# lickometer_1_0.net
KiCad netlist of a schematic drawn in EAGLE
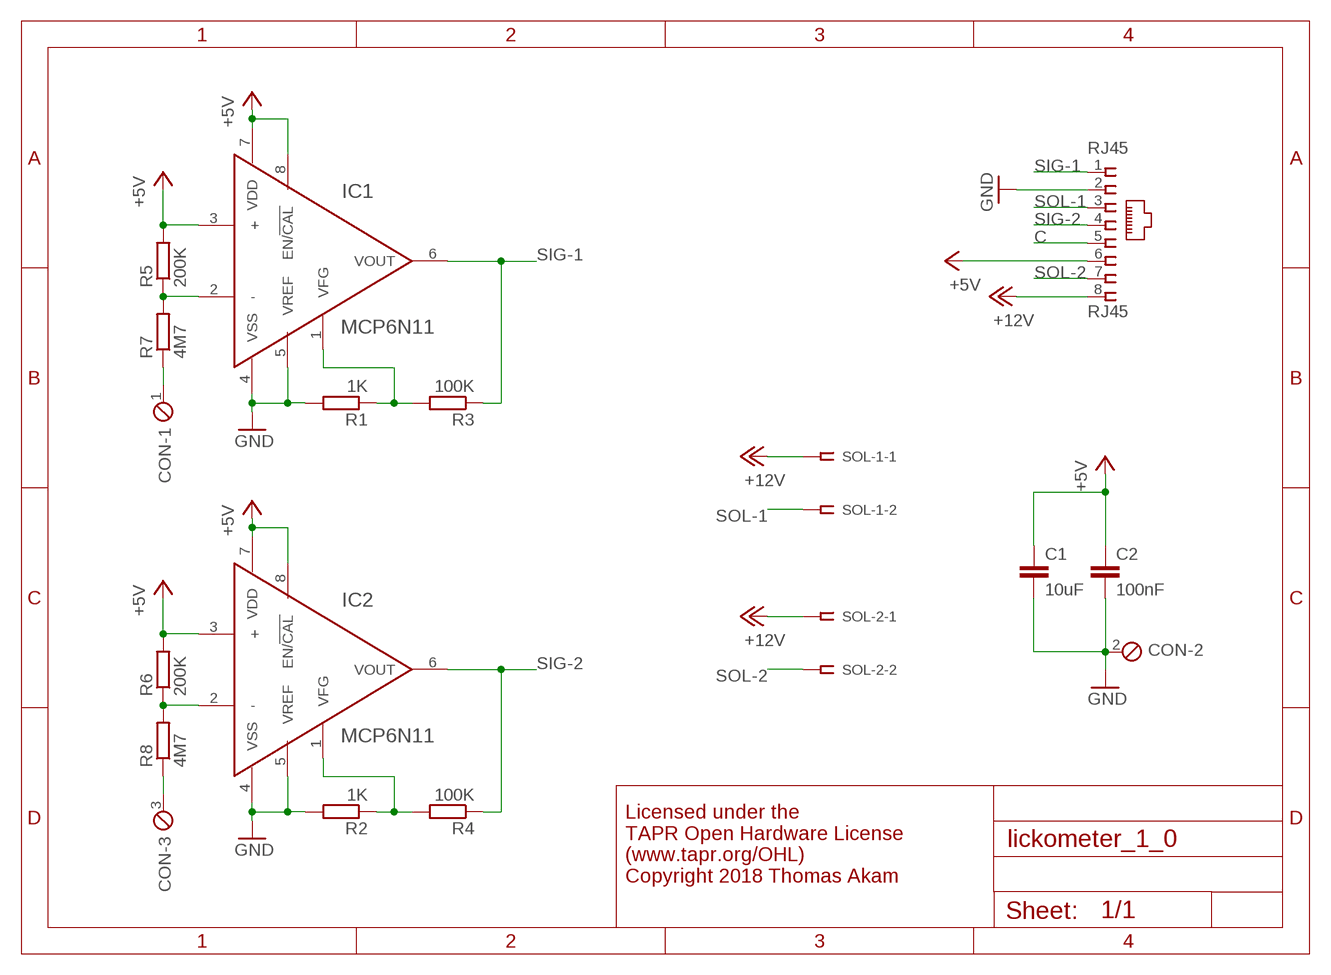
[diagram p0: schematic, sheet 1]

(export (version "E")
  (design (tool "Eeschema 10.0.6"))
  (components
    (comp (ref "C1")
      (value "10uF")
      (footprint "eagle-import:C1206")
      (libsource (lib "eagle-import") (part "C-EUC1206"))
    )
    (comp (ref "C2")
      (value "100nF")
      (footprint "eagle-import:C0805")
      (libsource (lib "eagle-import") (part "C-EUC0805"))
    )
    (comp (ref "CON")
      (value "MPT3")
      (footprint "eagle-import:3POL254")
      (libsource (lib "eagle-import") (part "MPT3"))
    )
    (comp (ref "IC1")
      (value "MCP6N11")
      (footprint "eagle-import:SOIC127P600X175-8N")
      (libsource (lib "eagle-import") (part "MCP6N11"))
    )
    (comp (ref "IC2")
      (value "MCP6N11")
      (footprint "eagle-import:SOIC127P600X175-8N")
      (libsource (lib "eagle-import") (part "MCP6N11"))
    )
    (comp (ref "R1")
      (value "1K")
      (footprint "eagle-import:R0805")
      (libsource (lib "eagle-import") (part "R-EU_R0805"))
    )
    (comp (ref "R2")
      (value "1K")
      (footprint "eagle-import:R0805")
      (libsource (lib "eagle-import") (part "R-EU_R0805"))
    )
    (comp (ref "R3")
      (value "100K")
      (footprint "eagle-import:R0805")
      (libsource (lib "eagle-import") (part "R-EU_R0805"))
    )
    (comp (ref "R4")
      (value "100K")
      (footprint "eagle-import:R0805")
      (libsource (lib "eagle-import") (part "R-EU_R0805"))
    )
    (comp (ref "R5")
      (value "200K")
      (footprint "eagle-import:R0805")
      (libsource (lib "eagle-import") (part "R-EU_R0805"))
    )
    (comp (ref "R6")
      (value "200K")
      (footprint "eagle-import:R0805")
      (libsource (lib "eagle-import") (part "R-EU_R0805"))
    )
    (comp (ref "R7")
      (value "4M7")
      (footprint "eagle-import:R0805")
      (libsource (lib "eagle-import") (part "R-EU_R0805"))
    )
    (comp (ref "R8")
      (value "4M7")
      (footprint "eagle-import:R0805")
      (libsource (lib "eagle-import") (part "R-EU_R0805"))
    )
    (comp (ref "RJ45")
      (value "RJ45")
      (footprint "eagle-import:RJ45-NO-SHIELD-VERTICAL")
      (libsource (lib "eagle-import") (part "RJ45VERTICAL"))
    )
    (comp (ref "SOL-1")
      (value "SSW-102-02-S-S-RA")
      (footprint "eagle-import:SSW-102-02-S-S-RA")
      (libsource (lib "eagle-import") (part "SSW-102-02-S-S-RA"))
    )
    (comp (ref "SOL-2")
      (value "SSW-102-02-S-S-RA")
      (footprint "eagle-import:SSW-102-02-S-S-RA")
      (libsource (lib "eagle-import") (part "SSW-102-02-S-S-RA"))
    )
  )
  (nets
    (net (code "1") (name "+5V") (class "Default")
      (node (ref "C1") (pin "1") (pinfunction "1_1") (pintype "passive"))
      (node (ref "C2") (pin "1") (pinfunction "1_1") (pintype "passive"))
      (node (ref "IC1") (pin "3") (pinfunction "+_3") (pintype "input"))
      (node (ref "IC1") (pin "7") (pinfunction "VDD_7") (pintype "power_in"))
      (node (ref "IC1") (pin "8") (pinfunction "EN/~{CAL}_8") (pintype "input"))
      (node (ref "IC2") (pin "3") (pinfunction "+_3") (pintype "input"))
      (node (ref "IC2") (pin "7") (pinfunction "VDD_7") (pintype "power_in"))
      (node (ref "IC2") (pin "8") (pinfunction "EN/~{CAL}_8") (pintype "input"))
      (node (ref "R5") (pin "2") (pinfunction "2_2") (pintype "passive"))
      (node (ref "R6") (pin "2") (pinfunction "2_2") (pintype "passive"))
      (node (ref "RJ45") (pin "6") (pinfunction "6_6") (pintype "passive"))
    )
    (net (code "2") (name "+12V") (class "Default")
      (node (ref "RJ45") (pin "8") (pinfunction "8_8") (pintype "passive"))
      (node (ref "SOL-1") (pin "1") (pinfunction "1_1") (pintype "passive"))
      (node (ref "SOL-2") (pin "1") (pinfunction "1_1") (pintype "passive"))
    )
    (net (code "3") (name "/C") (class "Default")
      (node (ref "RJ45") (pin "5") (pinfunction "5_5") (pintype "passive"))
    )
    (net (code "4") (name "/SIG-1") (class "Default")
      (node (ref "IC1") (pin "6") (pinfunction "VOUT_6") (pintype "output"))
      (node (ref "R3") (pin "1") (pinfunction "1_1") (pintype "passive"))
      (node (ref "RJ45") (pin "1") (pinfunction "1_1") (pintype "passive"))
    )
    (net (code "5") (name "/SIG-2") (class "Default")
      (node (ref "IC2") (pin "6") (pinfunction "VOUT_6") (pintype "output"))
      (node (ref "R4") (pin "1") (pinfunction "1_1") (pintype "passive"))
      (node (ref "RJ45") (pin "4") (pinfunction "4_4") (pintype "passive"))
    )
    (net (code "6") (name "/SOL-1") (class "Default")
      (node (ref "RJ45") (pin "3") (pinfunction "3_3") (pintype "passive"))
      (node (ref "SOL-1") (pin "2") (pinfunction "1_2") (pintype "passive"))
    )
    (net (code "7") (name "/SOL-2") (class "Default")
      (node (ref "RJ45") (pin "7") (pinfunction "7_7") (pintype "passive"))
      (node (ref "SOL-2") (pin "2") (pinfunction "1_2") (pintype "passive"))
    )
    (net (code "8") (name "GND") (class "Default")
      (node (ref "C1") (pin "2") (pinfunction "2_2") (pintype "passive"))
      (node (ref "C2") (pin "2") (pinfunction "2_2") (pintype "passive"))
      (node (ref "CON") (pin "2") (pinfunction "1_2") (pintype "passive"))
      (node (ref "IC1") (pin "4") (pinfunction "VSS_4") (pintype "power_in"))
      (node (ref "IC1") (pin "5") (pinfunction "VREF_5") (pintype "input"))
      (node (ref "IC2") (pin "4") (pinfunction "VSS_4") (pintype "power_in"))
      (node (ref "IC2") (pin "5") (pinfunction "VREF_5") (pintype "input"))
      (node (ref "R1") (pin "2") (pinfunction "2_2") (pintype "passive"))
      (node (ref "R2") (pin "2") (pinfunction "2_2") (pintype "passive"))
      (node (ref "RJ45") (pin "2") (pinfunction "2_2") (pintype "passive"))
    )
    (net (code "9") (name "Net-(CON-Pad1)") (class "Default")
      (node (ref "CON") (pin "1") (pinfunction "1_1") (pintype "passive"))
      (node (ref "R7") (pin "1") (pinfunction "1_1") (pintype "passive"))
    )
    (net (code "10") (name "Net-(CONC-1)") (class "Default")
      (node (ref "CON") (pin "3") (pinfunction "1_3") (pintype "passive"))
      (node (ref "R8") (pin "1") (pinfunction "1_1") (pintype "passive"))
    )
    (net (code "11") (name "Net-(IC1--)") (class "Default")
      (node (ref "IC1") (pin "2") (pinfunction "-_2") (pintype "input"))
      (node (ref "R5") (pin "1") (pinfunction "1_1") (pintype "passive"))
      (node (ref "R7") (pin "2") (pinfunction "2_2") (pintype "passive"))
    )
    (net (code "12") (name "Net-(IC1-VFG)") (class "Default")
      (node (ref "IC1") (pin "1") (pinfunction "VFG_1") (pintype "input"))
      (node (ref "R1") (pin "1") (pinfunction "1_1") (pintype "passive"))
      (node (ref "R3") (pin "2") (pinfunction "2_2") (pintype "passive"))
    )
    (net (code "13") (name "Net-(IC2--)") (class "Default")
      (node (ref "IC2") (pin "2") (pinfunction "-_2") (pintype "input"))
      (node (ref "R6") (pin "1") (pinfunction "1_1") (pintype "passive"))
      (node (ref "R8") (pin "2") (pinfunction "2_2") (pintype "passive"))
    )
    (net (code "14") (name "Net-(IC2-VFG)") (class "Default")
      (node (ref "IC2") (pin "1") (pinfunction "VFG_1") (pintype "input"))
      (node (ref "R2") (pin "1") (pinfunction "1_1") (pintype "passive"))
      (node (ref "R4") (pin "2") (pinfunction "2_2") (pintype "passive"))
    )
  )
)
